# bmp581.net
KiCad netlist of a schematic drawn in EAGLE
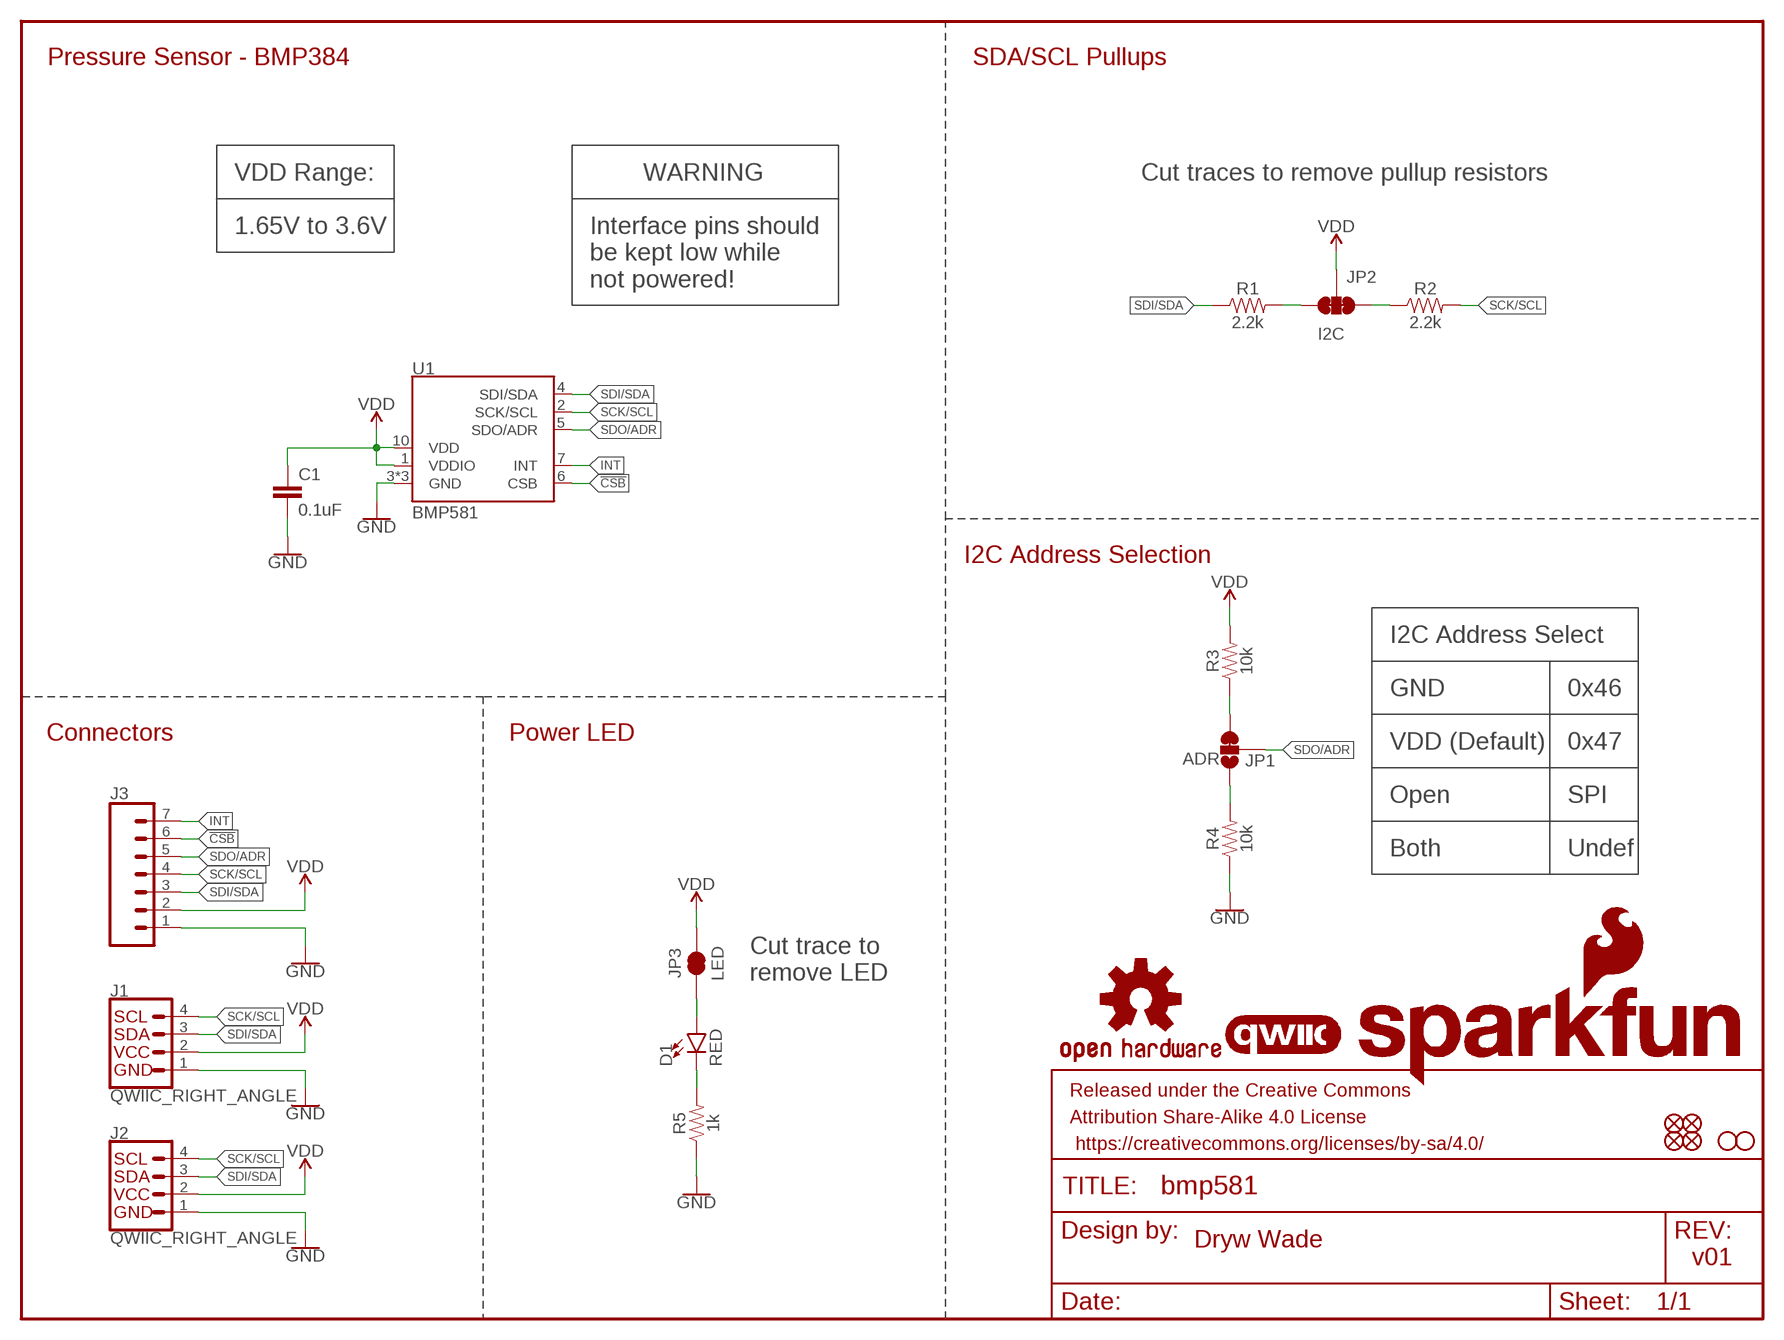
[diagram p0: schematic, sheet 1]

(export (version "E")
  (design (tool "Eeschema 10.0.6"))
  (components
    (comp (ref "C1")
      (value "0.1uF")
      (footprint "eagle-import:0603")
      (libsource (lib "eagle-import") (part "0.1UF-0603-25V-(+80/-20%)"))
    )
    (comp (ref "D1")
      (value "RED")
      (footprint "eagle-import:LED-0603")
      (libsource (lib "eagle-import") (part "LED-RED0603"))
    )
    (comp (ref "FD1")
      (value "FIDUCIAL1X2")
      (footprint "eagle-import:FIDUCIAL-1X2")
      (libsource (lib "eagle-import") (part "FIDUCIAL1X2"))
    )
    (comp (ref "FD2")
      (value "FIDUCIAL1X2")
      (footprint "eagle-import:FIDUCIAL-1X2")
      (libsource (lib "eagle-import") (part "FIDUCIAL1X2"))
    )
    (comp (ref "FD3")
      (value "FIDUCIAL1X2")
      (footprint "eagle-import:FIDUCIAL-1X2")
      (libsource (lib "eagle-import") (part "FIDUCIAL1X2"))
    )
    (comp (ref "FD4")
      (value "FIDUCIAL1X2")
      (footprint "eagle-import:FIDUCIAL-1X2")
      (libsource (lib "eagle-import") (part "FIDUCIAL1X2"))
    )
    (comp (ref "FRAME1")
      (value "FRAME-LETTER")
      (footprint "eagle-import:CREATIVE_COMMONS")
      (libsource (lib "eagle-import") (part "FRAME-LETTER"))
    )
    (comp (ref "H1")
      (value "STAND-OFF")
      (footprint "eagle-import:STAND-OFF")
      (libsource (lib "eagle-import") (part "STAND-OFF"))
    )
    (comp (ref "H2")
      (value "STAND-OFF")
      (footprint "eagle-import:STAND-OFF")
      (libsource (lib "eagle-import") (part "STAND-OFF"))
    )
    (comp (ref "J1")
      (value "QWIIC_RIGHT_ANGLE")
      (footprint "eagle-import:JST04_1MM_RA")
      (libsource (lib "eagle-import") (part "QWIIC_CONNECTORJS-1MM"))
    )
    (comp (ref "J2")
      (value "QWIIC_RIGHT_ANGLE")
      (footprint "eagle-import:JST04_1MM_RA")
      (libsource (lib "eagle-import") (part "QWIIC_CONNECTORJS-1MM"))
    )
    (comp (ref "J3")
      (value "CONN_07NO_SILK")
      (footprint "eagle-import:1X07_NO_SILK")
      (libsource (lib "eagle-import") (part "CONN_07NO_SILK"))
    )
    (comp (ref "JP1")
      (value "ADR")
      (footprint "eagle-import:SMT-JUMPER_3_1-NC_TRACE_SILK")
      (libsource (lib "eagle-import") (part "JUMPER-SMT_3_1-NC_TRACE_SILK"))
    )
    (comp (ref "JP2")
      (value "I2C")
      (footprint "eagle-import:SMT-JUMPER_3_2-NC_TRACE_SILK")
      (libsource (lib "eagle-import") (part "JUMPER-SMT_3_2-NC_TRACE_SILK"))
    )
    (comp (ref "JP3")
      (value "LED")
      (footprint "eagle-import:SMT-JUMPER_2_NC_TRACE_SILK")
      (libsource (lib "eagle-import") (part "JUMPER-SMT_2_NC_TRACE_SILK"))
    )
    (comp (ref "LOGO1")
      (value "OSHW-LOGOS")
      (footprint "eagle-import:OSHW-LOGO-S")
      (libsource (lib "eagle-import") (part "OSHW-LOGOS"))
    )
    (comp (ref "LOGO2")
      (value "SFE_LOGO_FLAME.2_INCH")
      (footprint "eagle-import:SFE_LOGO_FLAME_.2")
      (libsource (lib "eagle-import") (part "SFE_LOGO_FLAME.2_INCH"))
    )
    (comp (ref "LOGO3")
      (value "QWIIC_LOGO_5MM")
      (footprint "eagle-import:QWIIC_5MM")
      (libsource (lib "eagle-import") (part "QWIIC_LOGO_5MM"))
    )
    (comp (ref "LOGO4")
      (value "SFE_LOGO_NAME_FLAME.1_INCH")
      (footprint "eagle-import:SFE_LOGO_NAME_FLAME_.1")
      (libsource (lib "eagle-import") (part "SFE_LOGO_NAME_FLAME.1_INCH"))
    )
    (comp (ref "R1")
      (value "2.2k")
      (footprint "eagle-import:0603")
      (libsource (lib "eagle-import") (part "2.2KOHM-0603-1/10W-1%"))
    )
    (comp (ref "R2")
      (value "2.2k")
      (footprint "eagle-import:0603")
      (libsource (lib "eagle-import") (part "2.2KOHM-0603-1/10W-1%"))
    )
    (comp (ref "R3")
      (value "10k")
      (footprint "eagle-import:0603")
      (libsource (lib "eagle-import") (part "10KOHM-0603-1/10W-1%"))
    )
    (comp (ref "R4")
      (value "10k")
      (footprint "eagle-import:0603")
      (libsource (lib "eagle-import") (part "10KOHM-0603-1/10W-1%"))
    )
    (comp (ref "R5")
      (value "1k")
      (footprint "eagle-import:0603")
      (libsource (lib "eagle-import") (part "1KOHM-0603-1/10W-1%"))
    )
    (comp (ref "U1")
      (value "BMP581")
      (footprint "eagle-import:BMP581")
      (libsource (lib "eagle-import") (part "BMP581"))
    )
  )
  (nets
    (net (code "1") (name "/~{CSB}") (class "Default")
      (node (ref "J3") (pin "6") (pinfunction "6_6") (pintype "passive"))
      (node (ref "U1") (pin "6") (pinfunction "CSB_6") (pintype "input"))
    )
    (net (code "2") (name "GND") (class "Default")
      (node (ref "C1") (pin "2") (pinfunction "2_2") (pintype "passive"))
      (node (ref "J1") (pin "1") (pinfunction "1_1") (pintype "power_in"))
      (node (ref "J2") (pin "1") (pinfunction "1_1") (pintype "power_in"))
      (node (ref "J3") (pin "1") (pinfunction "1_1") (pintype "passive"))
      (node (ref "R4") (pin "1") (pinfunction "1_1") (pintype "passive"))
      (node (ref "R5") (pin "1") (pinfunction "1_1") (pintype "passive"))
      (node (ref "U1") (pin "3") (pinfunction "GND_3") (pintype "power_in"))
      (node (ref "U1") (pin "8") (pinfunction "GND_8") (pintype "power_in"))
      (node (ref "U1") (pin "9") (pinfunction "GND_9") (pintype "power_in"))
    )
    (net (code "3") (name "INT") (class "Default")
      (node (ref "J3") (pin "7") (pinfunction "7_7") (pintype "passive"))
      (node (ref "U1") (pin "7") (pinfunction "INT_7") (pintype "output"))
    )
    (net (code "4") (name "Net-(D1-PadA)") (class "Default")
      (node (ref "D1") (pin "A") (pinfunction "A_A") (pintype "passive"))
      (node (ref "JP3") (pin "1") (pinfunction "1_1") (pintype "passive"))
    )
    (net (code "5") (name "Net-(D1-PadC)") (class "Default")
      (node (ref "D1") (pin "C") (pinfunction "C_C") (pintype "passive"))
      (node (ref "R5") (pin "2") (pinfunction "2_2") (pintype "passive"))
    )
    (net (code "6") (name "Net-(JP1-Pad1)") (class "Default")
      (node (ref "JP1") (pin "1") (pinfunction "1_1") (pintype "passive"))
      (node (ref "R4") (pin "2") (pinfunction "2_2") (pintype "passive"))
    )
    (net (code "7") (name "Net-(JP1-Pad3)") (class "Default")
      (node (ref "JP1") (pin "3") (pinfunction "3_3") (pintype "passive"))
      (node (ref "R3") (pin "1") (pinfunction "1_1") (pintype "passive"))
    )
    (net (code "8") (name "Net-(JP2-Pad1)") (class "Default")
      (node (ref "JP2") (pin "1") (pinfunction "1_1") (pintype "passive"))
      (node (ref "R2") (pin "1") (pinfunction "1_1") (pintype "passive"))
    )
    (net (code "9") (name "Net-(JP2-Pad3)") (class "Default")
      (node (ref "JP2") (pin "3") (pinfunction "3_3") (pintype "passive"))
      (node (ref "R1") (pin "2") (pinfunction "2_2") (pintype "passive"))
    )
    (net (code "10") (name "SCK{slash}SCL") (class "Default")
      (node (ref "J1") (pin "4") (pinfunction "4_4") (pintype "passive"))
      (node (ref "J2") (pin "4") (pinfunction "4_4") (pintype "passive"))
      (node (ref "J3") (pin "4") (pinfunction "4_4") (pintype "passive"))
      (node (ref "R2") (pin "2") (pinfunction "2_2") (pintype "passive"))
      (node (ref "U1") (pin "2") (pinfunction "SCK/SCL_2") (pintype "bidirectional"))
    )
    (net (code "11") (name "SDI{slash}SDA") (class "Default")
      (node (ref "J1") (pin "3") (pinfunction "3_3") (pintype "passive"))
      (node (ref "J2") (pin "3") (pinfunction "3_3") (pintype "passive"))
      (node (ref "J3") (pin "3") (pinfunction "3_3") (pintype "passive"))
      (node (ref "R1") (pin "1") (pinfunction "1_1") (pintype "passive"))
      (node (ref "U1") (pin "4") (pinfunction "SDI/SDA_4") (pintype "bidirectional"))
    )
    (net (code "12") (name "SDO{slash}ADR") (class "Default")
      (node (ref "J3") (pin "5") (pinfunction "5_5") (pintype "passive"))
      (node (ref "JP1") (pin "2") (pinfunction "2_2") (pintype "passive"))
      (node (ref "U1") (pin "5") (pinfunction "SDO/ADR_5") (pintype "bidirectional"))
    )
    (net (code "13") (name "VDD") (class "Default")
      (node (ref "C1") (pin "1") (pinfunction "1_1") (pintype "passive"))
      (node (ref "J1") (pin "2") (pinfunction "2_2") (pintype "power_in"))
      (node (ref "J2") (pin "2") (pinfunction "2_2") (pintype "power_in"))
      (node (ref "J3") (pin "2") (pinfunction "2_2") (pintype "passive"))
      (node (ref "JP2") (pin "2") (pinfunction "2_2") (pintype "passive"))
      (node (ref "JP3") (pin "2") (pinfunction "2_2") (pintype "passive"))
      (node (ref "R3") (pin "2") (pinfunction "2_2") (pintype "passive"))
      (node (ref "U1") (pin "1") (pinfunction "VDDIO_1") (pintype "power_in"))
      (node (ref "U1") (pin "10") (pinfunction "VDD_10") (pintype "power_in"))
    )
  )
)
